# CapBank_Supercaps.net
KiCad netlist of a schematic drawn in Altium Designer
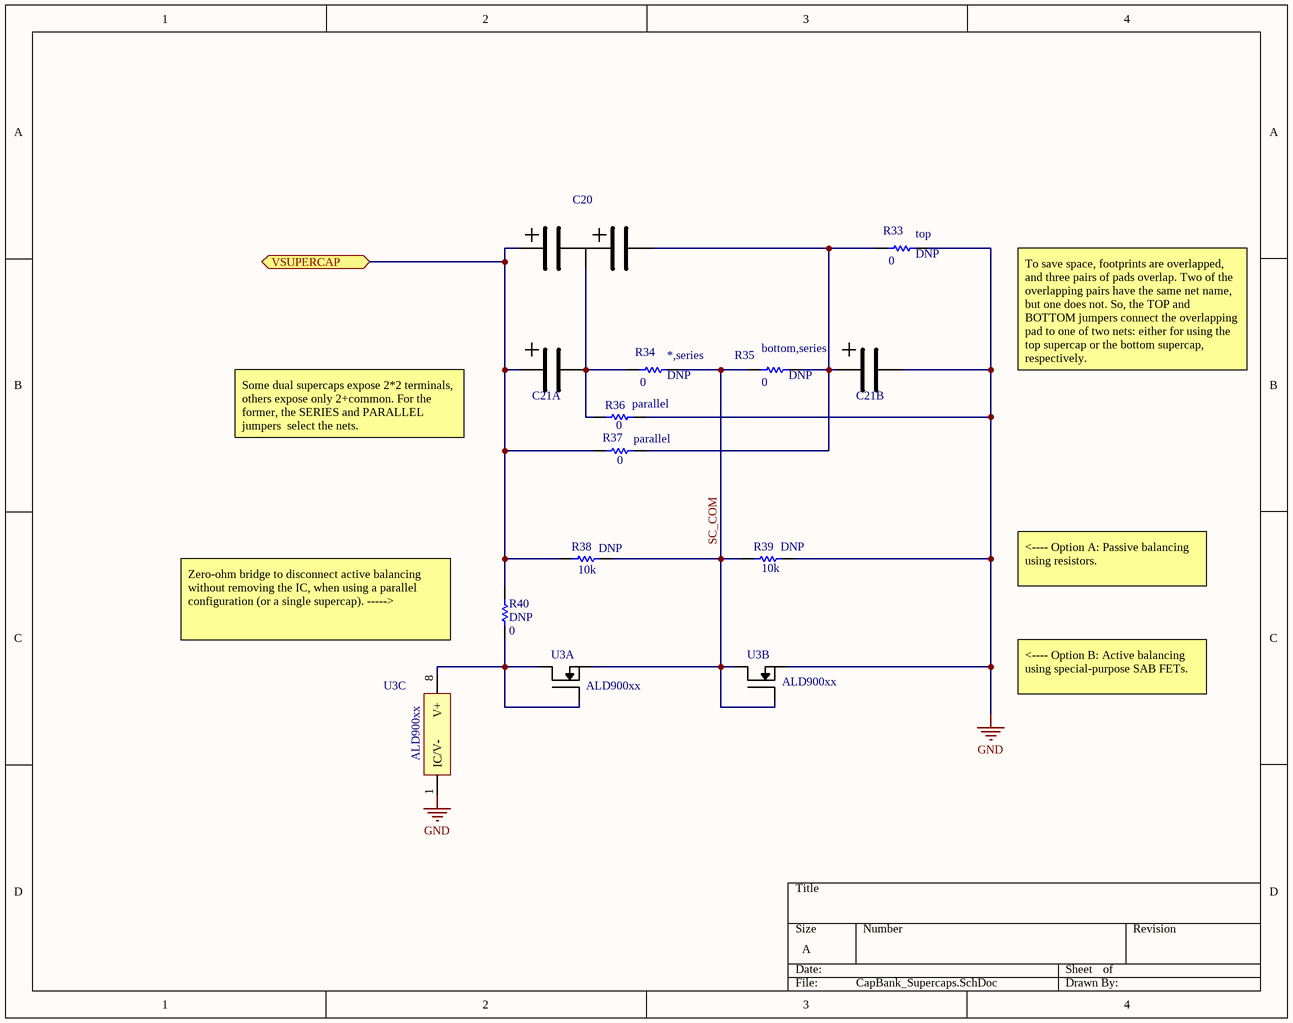
[diagram p0: CapBank_Supercaps.SchDoc]

(export (version "E")
  (design (tool "Eeschema 10.0.6"))
  (components
    (comp (ref "C20")
      (value "SUPERCAP_DUAL_SERIES")
      (footprint "SUPERCAP_DMT")
      (description "EDLC Supercap Dual with Balancing Terminal")
      (fields
        (field (name "DIGI-KEY PART NUMBER") "490-13208-ND")
        (field (name "DISTRIBUTOR PART NUMBER") "81-DMT3N4R2U224M3DT0")
      )
      (libsource (lib "Sprite") (part "SUPERCAP_DUAL_SERIES"))
    )
    (comp (ref "C21")
      (value "SUPERCAP_DUAL")
      (footprint "SUPERCAP_DMHA14R")
      (description "EDLC Supercap Dual")
      (fields
        (field (name "DIGI-KEY PART NUMBER") "490-17331-ND")
        (field (name "DISTRIBUTOR PART NUMBER") "81-DMHA14R5V353M4ATA")
      )
      (libsource (lib "Sprite") (part "SUPERCAP_DUAL"))
    )
    (comp (ref "R33")
      (value "0")
      (footprint "0603")
      (description "Chip Resistor (Surface Mount)")
      (fields
        (field (name "MANUFACTURER") "Yageo")
        (field (name "MANUFACTURER PART NUMBER") "RC0603JR-070RL")
        (field (name "NOTE") "DNP")
        (field (name "CONFIG") "top")
      )
      (libsource (lib "DRP_Basic_2014") (part "Res"))
    )
    (comp (ref "R34")
      (value "0")
      (footprint "0603")
      (description "Chip Resistor (Surface Mount)")
      (fields
        (field (name "MANUFACTURER") "Yageo")
        (field (name "MANUFACTURER PART NUMBER") "RC0603JR-070RL")
        (field (name "NOTE") "DNP")
        (field (name "CONFIG") "*,series")
      )
      (libsource (lib "DRP_Basic_2014") (part "Res"))
    )
    (comp (ref "R35")
      (value "0")
      (footprint "0603")
      (description "Chip Resistor (Surface Mount)")
      (fields
        (field (name "MANUFACTURER") "Yageo")
        (field (name "MANUFACTURER PART NUMBER") "RC0603JR-070RL")
        (field (name "NOTE") "DNP")
        (field (name "CONFIG") "bottom,series")
      )
      (libsource (lib "DRP_Basic_2014") (part "Res"))
    )
    (comp (ref "R36")
      (value "0")
      (footprint "0603")
      (description "Chip Resistor (Surface Mount)")
      (fields
        (field (name "MANUFACTURER") "Yageo")
        (field (name "MANUFACTURER PART NUMBER") "RC0603JR-070RL")
        (field (name "CONFIG") "parallel")
      )
      (libsource (lib "DRP_Basic_2014") (part "Res"))
    )
    (comp (ref "R37")
      (value "0")
      (footprint "0603")
      (description "Chip Resistor (Surface Mount)")
      (fields
        (field (name "MANUFACTURER") "Yageo")
        (field (name "MANUFACTURER PART NUMBER") "RC0603JR-070RL")
        (field (name "CONFIG") "parallel")
      )
      (libsource (lib "DRP_Basic_2014") (part "Res"))
    )
    (comp (ref "R38")
      (value "10k")
      (footprint "0603")
      (description "Chip Resistor (Surface Mount)")
      (fields
        (field (name "MANUFACTURER") "Yageo")
        (field (name "MANUFACTURER PART NUMBER") "RC0603FR-0710KL")
        (field (name "NOTE") "DNP")
      )
      (libsource (lib "DRP_Basic_2014") (part "Res"))
    )
    (comp (ref "R39")
      (value "10k")
      (footprint "0603")
      (description "Chip Resistor (Surface Mount)")
      (fields
        (field (name "MANUFACTURER") "Yageo")
        (field (name "MANUFACTURER PART NUMBER") "RC0603FR-0710KL")
        (field (name "NOTE") "DNP")
      )
      (libsource (lib "DRP_Basic_2014") (part "Res"))
    )
    (comp (ref "R40")
      (value "0")
      (footprint "0603")
      (description "Chip Resistor (Surface Mount)")
      (fields
        (field (name "MANUFACTURER") "Yageo")
        (field (name "MANUFACTURER PART NUMBER") "RC0603JR-070RL")
        (field (name "NOTE") "DNP")
      )
      (libsource (lib "DRP_Basic_2014") (part "Res"))
    )
    (comp (ref "U3")
      (value "ALD900xx")
      (footprint "SOIC8")
      (fields
        (field (name "DIGI-KEY PART NUMBER") "1014-1281-5-ND")
        (field (name "MANUFACTURER") "Advanced Linear Devices Inc.")
        (field (name "MANUFACTURER PART NUMBER") "ALD910021SAL")
        (field (name "DISTRIBUTOR PART NUMBER") "1014-1281-5-ND")
      )
      (libsource (lib "Sprite") (part "ALD9100xx"))
    )
  )
  (nets
    (net (code "1") (name "/SC_COM") (class "Default")
      (node (ref "R34") (pin "2") (pinfunction "2_2") (pintype "passive"))
      (node (ref "R35") (pin "1") (pinfunction "1_1") (pintype "passive"))
      (node (ref "R38") (pin "2") (pinfunction "2_2") (pintype "passive"))
      (node (ref "R39") (pin "1") (pinfunction "1_1") (pintype "passive"))
      (node (ref "U3") (pin "4") (pinfunction "SN1_4") (pintype "passive"))
      (node (ref "U3") (pin "6") (pinfunction "DN2_6") (pintype "passive"))
      (node (ref "U3") (pin "7") (pinfunction "GN2_7") (pintype "passive"))
    )
    (net (code "2") (name "/VSUPERCAP") (class "Default")
      (node (ref "C20") (pin "1") (pinfunction "P_1") (pintype "passive"))
      (node (ref "C21") (pin "1") (pinfunction "P2_1") (pintype "passive"))
      (node (ref "R37") (pin "1") (pinfunction "1_1") (pintype "passive"))
      (node (ref "R38") (pin "1") (pinfunction "1_1") (pintype "passive"))
      (node (ref "R40") (pin "1") (pinfunction "1_1") (pintype "passive"))
    )
    (net (code "3") (name "GND") (class "Default")
      (node (ref "C21") (pin "4") (pinfunction "N1_4") (pintype "passive"))
      (node (ref "R33") (pin "2") (pinfunction "2_2") (pintype "passive"))
      (node (ref "R36") (pin "2") (pinfunction "2_2") (pintype "passive"))
      (node (ref "R39") (pin "2") (pinfunction "2_2") (pintype "passive"))
      (node (ref "U3") (pin "1") (pinfunction "IC/V-_1") (pintype "passive"))
      (node (ref "U3") (pin "5") (pinfunction "SN2_5") (pintype "passive"))
    )
    (net (code "4") (name "Net-(C20-BAL)") (class "Default")
      (node (ref "C20") (pin "2") (pinfunction "BAL_2") (pintype "passive"))
      (node (ref "C21") (pin "2") (pinfunction "N2_2") (pintype "passive"))
      (node (ref "R34") (pin "1") (pinfunction "1_1") (pintype "passive"))
      (node (ref "R36") (pin "1") (pinfunction "1_1") (pintype "passive"))
    )
    (net (code "5") (name "Net-(C20-N)") (class "Default")
      (node (ref "C20") (pin "3") (pinfunction "N_3") (pintype "passive"))
      (node (ref "C21") (pin "3") (pinfunction "P1_3") (pintype "passive"))
      (node (ref "R33") (pin "1") (pinfunction "1_1") (pintype "passive"))
      (node (ref "R35") (pin "2") (pinfunction "2_2") (pintype "passive"))
      (node (ref "R37") (pin "2") (pinfunction "2_2") (pintype "passive"))
    )
    (net (code "6") (name "Net-(U3A-DN1)") (class "Default")
      (node (ref "R40") (pin "2") (pinfunction "2_2") (pintype "passive"))
      (node (ref "U3") (pin "2") (pinfunction "GN1_2") (pintype "passive"))
      (node (ref "U3") (pin "3") (pinfunction "DN1_3") (pintype "passive"))
      (node (ref "U3") (pin "8") (pinfunction "V+_8") (pintype "passive"))
    )
  )
)
